# SHIELD_W5500.net
KiCad netlist of a schematic drawn in Altium Designer
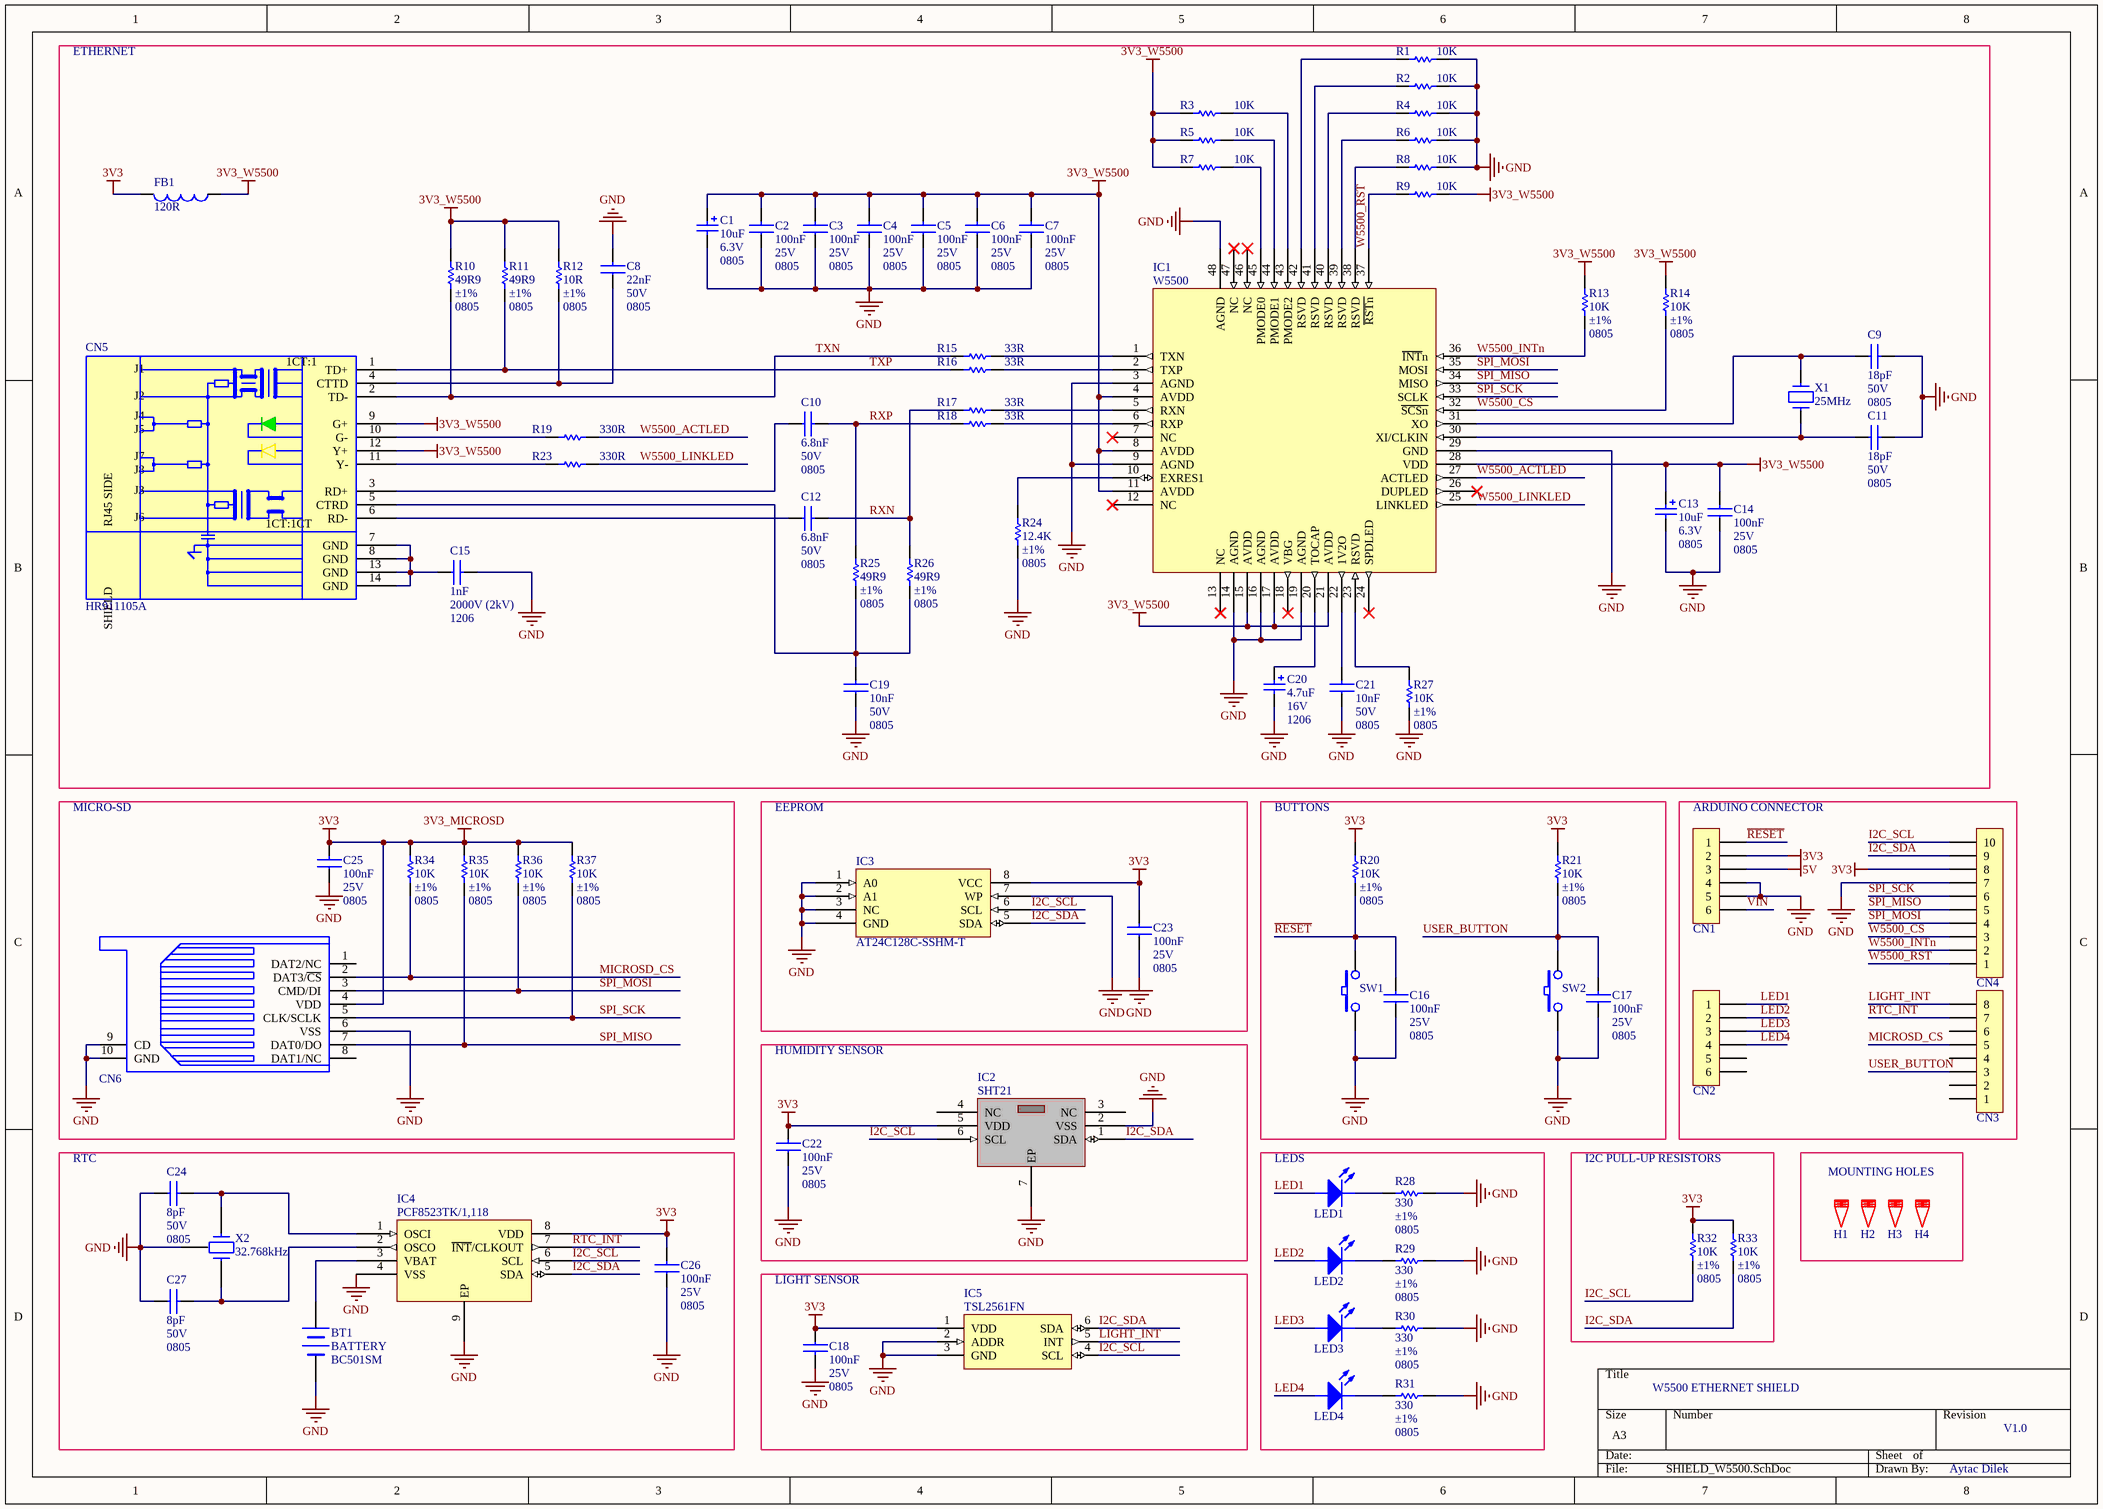
[diagram p0: SHIELD_W5500.SchDoc]

(export (version "E")
  (design (tool "Eeschema 10.0.6"))
  (components
    (comp (ref "BT1")
      (value "BATTERY")
      (footprint "MPD_BC501SM")
      (description "HOLDER COIN CELL FOR CR1220 SMD")
      (fields
        (field (name "PART NUMBER") "SBAT00011")
        (field (name "MANUFACTURER PART NUMBER") "BC501SM")
        (field (name "VOLTAGE") "3V")
      )
      (libsource (lib "ComponentDatabase") (part "BATTERY"))
    )
    (comp (ref "C1")
      (value "10uF")
      (footprint "CAPMP2013X12N_EIA-0805_CASE-R")
      (description "CAP TANT 10UF 6.3V 10% 0805")
      (fields
        (field (name "PART NUMBER") "SCAP01400004")
        (field (name "TOLERANCE") "±10%")
        (field (name "VOLTAGE - RATED") "6.3V")
        (field (name "PACKAGE / CASE") "0805")
      )
      (libsource (lib "ComponentDatabase") (part "CAP_P"))
    )
    (comp (ref "C2")
      (value "CAP_NP")
      (footprint "CAPC2012X100N_EIA0805")
      (description "CAP CER 0.1UF 25V X7R 0805")
      (fields
        (field (name "PART NUMBER") "SCAP00300093")
        (field (name "CAPACITANCE") "100nF")
        (field (name "TOLERANCE") "±10%")
        (field (name "VOLTAGE - RATED") "25V")
        (field (name "PACKAGE / CASE") "0805")
      )
      (libsource (lib "ComponentDatabase") (part "CAP_NP"))
    )
    (comp (ref "C3")
      (value "CAP_NP")
      (footprint "CAPC2012X100N_EIA0805")
      (description "CAP CER 0.1UF 25V X7R 0805")
      (fields
        (field (name "PART NUMBER") "SCAP00300093")
        (field (name "CAPACITANCE") "100nF")
        (field (name "TOLERANCE") "±10%")
        (field (name "VOLTAGE - RATED") "25V")
        (field (name "PACKAGE / CASE") "0805")
      )
      (libsource (lib "ComponentDatabase") (part "CAP_NP"))
    )
    (comp (ref "C4")
      (value "CAP_NP")
      (footprint "CAPC2012X100N_EIA0805")
      (description "CAP CER 0.1UF 25V X7R 0805")
      (fields
        (field (name "PART NUMBER") "SCAP00300093")
        (field (name "CAPACITANCE") "100nF")
        (field (name "TOLERANCE") "±10%")
        (field (name "VOLTAGE - RATED") "25V")
        (field (name "PACKAGE / CASE") "0805")
      )
      (libsource (lib "ComponentDatabase") (part "CAP_NP"))
    )
    (comp (ref "C5")
      (value "CAP_NP")
      (footprint "CAPC2012X100N_EIA0805")
      (description "CAP CER 0.1UF 25V X7R 0805")
      (fields
        (field (name "PART NUMBER") "SCAP00300093")
        (field (name "CAPACITANCE") "100nF")
        (field (name "TOLERANCE") "±10%")
        (field (name "VOLTAGE - RATED") "25V")
        (field (name "PACKAGE / CASE") "0805")
      )
      (libsource (lib "ComponentDatabase") (part "CAP_NP"))
    )
    (comp (ref "C6")
      (value "CAP_NP")
      (footprint "CAPC2012X100N_EIA0805")
      (description "CAP CER 0.1UF 25V X7R 0805")
      (fields
        (field (name "PART NUMBER") "SCAP00300093")
        (field (name "CAPACITANCE") "100nF")
        (field (name "TOLERANCE") "±10%")
        (field (name "VOLTAGE - RATED") "25V")
        (field (name "PACKAGE / CASE") "0805")
      )
      (libsource (lib "ComponentDatabase") (part "CAP_NP"))
    )
    (comp (ref "C7")
      (value "CAP_NP")
      (footprint "CAPC2012X100N_EIA0805")
      (description "CAP CER 0.1UF 25V X7R 0805")
      (fields
        (field (name "PART NUMBER") "SCAP00300093")
        (field (name "CAPACITANCE") "100nF")
        (field (name "TOLERANCE") "±10%")
        (field (name "VOLTAGE - RATED") "25V")
        (field (name "PACKAGE / CASE") "0805")
      )
      (libsource (lib "ComponentDatabase") (part "CAP_NP"))
    )
    (comp (ref "C8")
      (value "CAP_NP")
      (footprint "CAPC2012X100N_EIA0805")
      (description "CAP CER 0.022UF 50V X7R 0805")
      (fields
        (field (name "PART NUMBER") "SCAP00300087")
        (field (name "CAPACITANCE") "22nF")
        (field (name "TOLERANCE") "±10%")
        (field (name "VOLTAGE - RATED") "50V")
        (field (name "PACKAGE / CASE") "0805")
      )
      (libsource (lib "ComponentDatabase") (part "CAP_NP"))
    )
    (comp (ref "C9")
      (value "CAP_NP")
      (footprint "CAPC2012X100N_EIA0805")
      (description "CAP CER 18PF 50V NP0 0805")
      (fields
        (field (name "PART NUMBER") "SCAP00300040")
        (field (name "CAPACITANCE") "18pF")
        (field (name "TOLERANCE") "±5%")
        (field (name "VOLTAGE - RATED") "50V")
        (field (name "PACKAGE / CASE") "0805")
      )
      (libsource (lib "ComponentDatabase") (part "CAP_NP"))
    )
    (comp (ref "C10")
      (value "CAP_NP")
      (footprint "CAPC2012X100N_EIA0805")
      (description "CAP CER 6800PF 50V X7R 0805")
      (fields
        (field (name "PART NUMBER") "SCAP00300083")
        (field (name "CAPACITANCE") "6.8nF")
        (field (name "TOLERANCE") "±10%")
        (field (name "VOLTAGE - RATED") "50V")
        (field (name "PACKAGE / CASE") "0805")
      )
      (libsource (lib "ComponentDatabase") (part "CAP_NP"))
    )
    (comp (ref "C11")
      (value "CAP_NP")
      (footprint "CAPC2012X100N_EIA0805")
      (description "CAP CER 18PF 50V NP0 0805")
      (fields
        (field (name "PART NUMBER") "SCAP00300040")
        (field (name "CAPACITANCE") "18pF")
        (field (name "TOLERANCE") "±5%")
        (field (name "VOLTAGE - RATED") "50V")
        (field (name "PACKAGE / CASE") "0805")
      )
      (libsource (lib "ComponentDatabase") (part "CAP_NP"))
    )
    (comp (ref "C12")
      (value "CAP_NP")
      (footprint "CAPC2012X100N_EIA0805")
      (description "CAP CER 6800PF 50V X7R 0805")
      (fields
        (field (name "PART NUMBER") "SCAP00300083")
        (field (name "CAPACITANCE") "6.8nF")
        (field (name "TOLERANCE") "±10%")
        (field (name "VOLTAGE - RATED") "50V")
        (field (name "PACKAGE / CASE") "0805")
      )
      (libsource (lib "ComponentDatabase") (part "CAP_NP"))
    )
    (comp (ref "C13")
      (value "10uF")
      (footprint "CAPMP2013X12N_EIA-0805_CASE-R")
      (description "CAP TANT 10UF 6.3V 10% 0805")
      (fields
        (field (name "PART NUMBER") "SCAP01400004")
        (field (name "TOLERANCE") "±10%")
        (field (name "VOLTAGE - RATED") "6.3V")
        (field (name "PACKAGE / CASE") "0805")
      )
      (libsource (lib "ComponentDatabase") (part "CAP_P"))
    )
    (comp (ref "C14")
      (value "CAP_NP")
      (footprint "CAPC2012X100N_EIA0805")
      (description "CAP CER 0.1UF 25V X7R 0805")
      (fields
        (field (name "PART NUMBER") "SCAP00300093")
        (field (name "CAPACITANCE") "100nF")
        (field (name "TOLERANCE") "±10%")
        (field (name "VOLTAGE - RATED") "25V")
        (field (name "PACKAGE / CASE") "0805")
      )
      (libsource (lib "ComponentDatabase") (part "CAP_NP"))
    )
    (comp (ref "C15")
      (value "1nF")
      (footprint "CAPC3216X125N_EIA1206")
      (description "CAP CER 1000PF 2KV X7R 1206")
      (fields
        (field (name "PART NUMBER") "SCAP00410036")
        (field (name "TOLERANCE") "±10%")
        (field (name "VOLTAGE - RATED") "2000V (2kV)")
        (field (name "PACKAGE / CASE") "1206")
      )
      (libsource (lib "ComponentDatabase") (part "CAP_NP"))
    )
    (comp (ref "C16")
      (value "CAP_NP")
      (footprint "CAPC2012X100N_EIA0805")
      (description "CAP CER 0.1UF 25V X7R 0805")
      (fields
        (field (name "PART NUMBER") "SCAP00300093")
        (field (name "CAPACITANCE") "100nF")
        (field (name "VOLTAGE - RATED") "25V")
        (field (name "PACKAGE / CASE") "0805")
        (field (name "TOLERANCE") "±10%")
      )
      (libsource (lib "ComponentDatabase") (part "CAP_NP"))
    )
    (comp (ref "C17")
      (value "CAP_NP")
      (footprint "CAPC2012X100N_EIA0805")
      (description "CAP CER 0.1UF 25V X7R 0805")
      (fields
        (field (name "PART NUMBER") "SCAP00300093")
        (field (name "CAPACITANCE") "100nF")
        (field (name "VOLTAGE - RATED") "25V")
        (field (name "PACKAGE / CASE") "0805")
        (field (name "TOLERANCE") "±10%")
      )
      (libsource (lib "ComponentDatabase") (part "CAP_NP"))
    )
    (comp (ref "C18")
      (value "CAP_NP")
      (footprint "CAPC2012X100N_EIA0805")
      (description "CAP CER 0.1UF 25V X7R 0805")
      (fields
        (field (name "PART NUMBER") "SCAP00300093")
        (field (name "CAPACITANCE") "100nF")
        (field (name "TOLERANCE") "±10%")
        (field (name "VOLTAGE - RATED") "25V")
        (field (name "PACKAGE / CASE") "0805")
      )
      (libsource (lib "ComponentDatabase") (part "CAP_NP"))
    )
    (comp (ref "C19")
      (value "CAP_NP")
      (footprint "CAPC2012X100N_EIA0805")
      (description "CAP CER 10000PF 50V X7R 0805")
      (fields
        (field (name "PART NUMBER") "SCAP00300085")
        (field (name "CAPACITANCE") "10nF")
        (field (name "TOLERANCE") "±10%")
        (field (name "VOLTAGE - RATED") "50V")
        (field (name "PACKAGE / CASE") "0805")
      )
      (libsource (lib "ComponentDatabase") (part "CAP_NP"))
    )
    (comp (ref "C20")
      (value "4.7uF")
      (footprint "CAPMP3216X16N_EIA-1206_CASE-A")
      (description "CAP TANT 4.7UF 16V 10% 1206")
      (fields
        (field (name "PART NUMBER") "SCAP01400003")
        (field (name "TOLERANCE") "±10%")
        (field (name "VOLTAGE - RATED") "16V")
        (field (name "PACKAGE / CASE") "1206")
      )
      (libsource (lib "ComponentDatabase") (part "CAP_P"))
    )
    (comp (ref "C21")
      (value "CAP_NP")
      (footprint "CAPC2012X100N_EIA0805")
      (description "CAP CER 10000PF 50V X7R 0805")
      (fields
        (field (name "PART NUMBER") "SCAP00300085")
        (field (name "CAPACITANCE") "10nF")
        (field (name "TOLERANCE") "±10%")
        (field (name "VOLTAGE - RATED") "50V")
        (field (name "PACKAGE / CASE") "0805")
      )
      (libsource (lib "ComponentDatabase") (part "CAP_NP"))
    )
    (comp (ref "C22")
      (value "CAP_NP")
      (footprint "CAPC2012X100N_EIA0805")
      (description "CAP CER 0.1UF 25V X7R 0805")
      (fields
        (field (name "PART NUMBER") "SCAP00300093")
        (field (name "CAPACITANCE") "100nF")
        (field (name "TOLERANCE") "±10%")
        (field (name "VOLTAGE - RATED") "25V")
        (field (name "PACKAGE / CASE") "0805")
      )
      (libsource (lib "ComponentDatabase") (part "CAP_NP"))
    )
    (comp (ref "C23")
      (value "CAP_NP")
      (footprint "CAPC2012X100N_EIA0805")
      (description "CAP CER 0.1UF 25V X7R 0805")
      (fields
        (field (name "PART NUMBER") "SCAP00300093")
        (field (name "CAPACITANCE") "100nF")
        (field (name "VOLTAGE - RATED") "25V")
        (field (name "PACKAGE / CASE") "0805")
        (field (name "TOLERANCE") "±10%")
      )
      (libsource (lib "ComponentDatabase") (part "CAP_NP"))
    )
    (comp (ref "C24")
      (value "CAP_NP")
      (footprint "CAPC2012X100N_EIA0805")
      (description "CAP CER 8PF 50V NP0 0805")
      (fields
        (field (name "PART NUMBER") "SCAP00300030")
        (field (name "CAPACITANCE") "8pF")
        (field (name "VOLTAGE - RATED") "50V")
        (field (name "PACKAGE / CASE") "0805")
        (field (name "TOLERANCE") "±0.25pF")
      )
      (libsource (lib "ComponentDatabase") (part "CAP_NP"))
    )
    (comp (ref "C25")
      (value "CAP_NP")
      (footprint "CAPC2012X100N_EIA0805")
      (description "CAP CER 0.1UF 25V X7R 0805")
      (fields
        (field (name "PART NUMBER") "SCAP00300093")
        (field (name "CAPACITANCE") "100nF")
        (field (name "VOLTAGE - RATED") "25V")
        (field (name "PACKAGE / CASE") "0805")
        (field (name "TOLERANCE") "±10%")
      )
      (libsource (lib "ComponentDatabase") (part "CAP_NP"))
    )
    (comp (ref "C26")
      (value "CAP_NP")
      (footprint "CAPC2012X100N_EIA0805")
      (description "CAP CER 0.1UF 25V X7R 0805")
      (fields
        (field (name "PART NUMBER") "SCAP00300093")
        (field (name "CAPACITANCE") "100nF")
        (field (name "VOLTAGE - RATED") "25V")
        (field (name "PACKAGE / CASE") "0805")
        (field (name "TOLERANCE") "±10%")
      )
      (libsource (lib "ComponentDatabase") (part "CAP_NP"))
    )
    (comp (ref "C27")
      (value "CAP_NP")
      (footprint "CAPC2012X100N_EIA0805")
      (description "CAP CER 8PF 50V NP0 0805")
      (fields
        (field (name "PART NUMBER") "SCAP00300030")
        (field (name "CAPACITANCE") "8pF")
        (field (name "VOLTAGE - RATED") "50V")
        (field (name "PACKAGE / CASE") "0805")
        (field (name "TOLERANCE") "±0.25pF")
      )
      (libsource (lib "ComponentDatabase") (part "CAP_NP"))
    )
    (comp (ref "CN1")
      (value "HDR_1X6")
      (footprint "HDRFV6W70P254_1X6_1524X254X1118P")
      (description "CONN ARDUINO HEADER .0100\" 6POS")
      (fields (field (name "PART NUMBER") "SCON00124"))
      (libsource (lib "ComponentDatabase") (part "HDR_1X6"))
    )
    (comp (ref "CN2")
      (value "HDR_1X6")
      (footprint "HDRFV6W70P254_1X6_1524X254X1118P")
      (description "CONN ARDUINO HEADER .0100\" 6POS")
      (fields (field (name "PART NUMBER") "SCON00124"))
      (libsource (lib "ComponentDatabase") (part "HDR_1X6"))
    )
    (comp (ref "CN3")
      (value "HDR_1X8")
      (footprint "HDRFV8W70P254_1X8_2032X254X1118P")
      (description "CONN ARDUINO HEADER .0100\" 8POS")
      (fields (field (name "PART NUMBER") "SCON00125"))
      (libsource (lib "ComponentDatabase") (part "HDR_1X8"))
    )
    (comp (ref "CN4")
      (value "HDR_1X10")
      (footprint "HDRFV10W70P254_1X10_2540X254X1118P")
      (description "CONN ARDUINO HEADER .0100\" 10POS")
      (fields (field (name "PART NUMBER") "SCON00126"))
      (libsource (lib "ComponentDatabase") (part "HDR_1X10"))
    )
    (comp (ref "CN5")
      (value "HR911105A")
      (footprint "HANRUN_HR911105A")
      (description "CONN MAGJACK 1PORT 100 BASE-T")
      (fields (field (name "PART NUMBER") "SCON00127"))
      (libsource (lib "ComponentDatabase") (part "HR911105A"))
    )
    (comp (ref "CN6")
      (value "MICRO-SD")
      (footprint "MICRO-SD-SELF-EJECT")
      (description "CONN MICRO SD CARD PUSH-PUSH R/A")
      (fields (field (name "PART NUMBER") "SCON00094") (field (name "MANUFACTURER") "TransFlash"))
      (libsource (lib "ComponentDatabase") (part "MICRO-SD"))
    )
    (comp (ref "FB1")
      (value "BEAD")
      (footprint "FILC2012X100N_EIA0805")
      (description "FERRITE CHIP POWER 120 OHM SMD")
      (fields
        (field (name "PART NUMBER") "SFIL00005")
        (field (name "IMPEDANCE") "120R")
        (field (name "MANUFACTURER") "Laird-Signal Integrity Products")
      )
      (libsource (lib "ComponentDatabase") (part "BEAD"))
    )
    (comp (ref "H1")
      (value "HOLES")
      (footprint "HOLE_125MIL")
      (description "Holes")
      (fields (field (name "PART NUMBER") "SMSC00005"))
      (libsource (lib "ComponentDatabase") (part "HOLES"))
    )
    (comp (ref "H2")
      (value "HOLES")
      (footprint "HOLE_125MIL")
      (description "Holes")
      (fields (field (name "PART NUMBER") "SMSC00005"))
      (libsource (lib "ComponentDatabase") (part "HOLES"))
    )
    (comp (ref "H3")
      (value "HOLES")
      (footprint "HOLE_125MIL")
      (description "Holes")
      (fields (field (name "PART NUMBER") "SMSC00005"))
      (libsource (lib "ComponentDatabase") (part "HOLES"))
    )
    (comp (ref "H4")
      (value "HOLES")
      (footprint "HOLE_125MIL")
      (description "Holes")
      (fields (field (name "PART NUMBER") "SMSC00005"))
      (libsource (lib "ComponentDatabase") (part "HOLES"))
    )
    (comp (ref "IC1")
      (value "W5500")
      (footprint "QFP50P900X900X160-48N")
      (description "IC CTLR 3-1 ETH TCP/IP 48LQFP")
      (fields
        (field (name "PART NUMBER") "SIC00138")
        (field (name "MANUFACTURER PART NUMBER") "W5500")
        (field (name "MANUFACTURER") "WIZnet")
      )
      (libsource (lib "ComponentDatabase") (part "W5500"))
    )
    (comp (ref "IC2")
      (value "SHT21")
      (footprint "SHT21")
      (description "HUMIDITY AND TEMPERATURE SENSOR")
      (fields
        (field (name "PART NUMBER") "SSEN00014")
        (field (name "VOLTAGE") "2.1 V ~ 3.6 V")
        (field (name "MANUFACTURER PART NUMBER") "SHT21")
      )
      (libsource (lib "ComponentDatabase") (part "SHT21"))
    )
    (comp (ref "IC3")
      (value "AT24C128")
      (footprint "SOIC127P600X175-8N")
      (description "IC EEPROM 128KBIT 1MHZ 8SOIC")
      (fields
        (field (name "PART NUMBER") "SMEM00014")
        (field (name "VOLTAGE") "1.7 V ~ 5.5 V")
        (field (name "MANUFACTURER PART NUMBER") "AT24C128C-SSHM-T")
      )
      (libsource (lib "ComponentDatabase") (part "AT24C128"))
    )
    (comp (ref "IC4")
      (value "PCF8523TK/1,118")
      (footprint "SON80P400X100_HS-9N_[NXP]SOT909-1")
      (description "IC RTC CLK/CALENDAR I2C 8-HVSON")
      (fields
        (field (name "PART NUMBER") "SIC00133")
        (field (name "MANUFACTURER PART NUMBER") "PCF8523TK/1,118")
        (field (name "MANUFACTURER") "NXP Semiconductors")
      )
      (libsource (lib "ComponentDatabase") (part "PCF8523TK/1,118"))
    )
    (comp (ref "IC5")
      (value "TSL256x")
      (footprint "DFN-6")
      (description "IC LIGHT TO DGTL CONV 6-DFN")
      (fields
        (field (name "PART NUMBER") "SSEN00013")
        (field (name "VOLTAGE") "2.7 V ~ 3.6 V")
        (field (name "MANUFACTURER PART NUMBER") "TSL2561FN")
      )
      (libsource (lib "ComponentDatabase") (part "TSL256x"))
    )
    (comp (ref "LED1")
      (value "LED")
      (footprint "LEDC2012X70N_EIA0805_RED")
      (description "LED SUPER RED CLR THIN 0805 SMD")
      (fields (field (name "PART NUMBER") "SOPT00004") (field (name "MANUFACTURER") "Lite-On Inc"))
      (libsource (lib "ComponentDatabase") (part "LED"))
    )
    (comp (ref "LED2")
      (value "LED")
      (footprint "LEDC2012X70N_EIA0805_RED")
      (description "LED SUPER RED CLR THIN 0805 SMD")
      (fields (field (name "PART NUMBER") "SOPT00004") (field (name "MANUFACTURER") "Lite-On Inc"))
      (libsource (lib "ComponentDatabase") (part "LED"))
    )
    (comp (ref "LED3")
      (value "LED")
      (footprint "LEDC2012X70N_EIA0805_RED")
      (description "LED SUPER RED CLR THIN 0805 SMD")
      (fields (field (name "PART NUMBER") "SOPT00004") (field (name "MANUFACTURER") "Lite-On Inc"))
      (libsource (lib "ComponentDatabase") (part "LED"))
    )
    (comp (ref "LED4")
      (value "LED")
      (footprint "LEDC2012X70N_EIA0805_RED")
      (description "LED SUPER RED CLR THIN 0805 SMD")
      (fields (field (name "PART NUMBER") "SOPT00004") (field (name "MANUFACTURER") "Lite-On Inc"))
      (libsource (lib "ComponentDatabase") (part "LED"))
    )
    (comp (ref "R1")
      (value "10K")
      (footprint "RESC2013X65N_EIA0805")
      (description "RES SMD 10K OHM 1% 1/8W 0805")
      (fields (field (name "PART NUMBER") "SRES03010098") (field (name "TOLERANCE") "±1%"))
      (libsource (lib "ComponentDatabase") (part "RES"))
    )
    (comp (ref "R2")
      (value "10K")
      (footprint "RESC2013X65N_EIA0805")
      (description "RES SMD 10K OHM 1% 1/8W 0805")
      (fields (field (name "PART NUMBER") "SRES03010098") (field (name "TOLERANCE") "±1%"))
      (libsource (lib "ComponentDatabase") (part "RES"))
    )
    (comp (ref "R3")
      (value "10K")
      (footprint "RESC2013X65N_EIA0805")
      (description "RES SMD 10K OHM 1% 1/8W 0805")
      (fields (field (name "PART NUMBER") "SRES03010098") (field (name "TOLERANCE") "±1%"))
      (libsource (lib "ComponentDatabase") (part "RES"))
    )
    (comp (ref "R4")
      (value "10K")
      (footprint "RESC2013X65N_EIA0805")
      (description "RES SMD 10K OHM 1% 1/8W 0805")
      (fields (field (name "PART NUMBER") "SRES03010098") (field (name "TOLERANCE") "±1%"))
      (libsource (lib "ComponentDatabase") (part "RES"))
    )
    (comp (ref "R5")
      (value "10K")
      (footprint "RESC2013X65N_EIA0805")
      (description "RES SMD 10K OHM 1% 1/8W 0805")
      (fields (field (name "PART NUMBER") "SRES03010098") (field (name "TOLERANCE") "±1%"))
      (libsource (lib "ComponentDatabase") (part "RES"))
    )
    (comp (ref "R6")
      (value "10K")
      (footprint "RESC2013X65N_EIA0805")
      (description "RES SMD 10K OHM 1% 1/8W 0805")
      (fields (field (name "PART NUMBER") "SRES03010098") (field (name "TOLERANCE") "±1%"))
      (libsource (lib "ComponentDatabase") (part "RES"))
    )
    (comp (ref "R7")
      (value "10K")
      (footprint "RESC2013X65N_EIA0805")
      (description "RES SMD 10K OHM 1% 1/8W 0805")
      (fields (field (name "PART NUMBER") "SRES03010098") (field (name "TOLERANCE") "±1%"))
      (libsource (lib "ComponentDatabase") (part "RES"))
    )
    (comp (ref "R8")
      (value "10K")
      (footprint "RESC2013X65N_EIA0805")
      (description "RES SMD 10K OHM 1% 1/8W 0805")
      (fields (field (name "PART NUMBER") "SRES03010098") (field (name "TOLERANCE") "±1%"))
      (libsource (lib "ComponentDatabase") (part "RES"))
    )
    (comp (ref "R9")
      (value "10K")
      (footprint "RESC2013X65N_EIA0805")
      (description "RES SMD 10K OHM 1% 1/8W 0805")
      (fields (field (name "PART NUMBER") "SRES03010098") (field (name "TOLERANCE") "±1%"))
      (libsource (lib "ComponentDatabase") (part "RES"))
    )
    (comp (ref "R10")
      (value "49R9")
      (footprint "RESC2013X65N_EIA0805")
      (description "RES SMD 49.9 OHM 1% 1/8W 0805")
      (fields
        (field (name "PART NUMBER") "SRES03030081")
        (field (name "TOLERANCE") "±1%")
        (field (name "PACKAGE / CASE") "0805")
        (field (name "MANUFACTURER") "Samsung Electro-Mechanics America, Inc.")
      )
      (libsource (lib "ComponentDatabase") (part "RES"))
    )
    (comp (ref "R11")
      (value "49R9")
      (footprint "RESC2013X65N_EIA0805")
      (description "RES SMD 49.9 OHM 1% 1/8W 0805")
      (fields
        (field (name "PART NUMBER") "SRES03030081")
        (field (name "TOLERANCE") "±1%")
        (field (name "PACKAGE / CASE") "0805")
        (field (name "MANUFACTURER") "Samsung Electro-Mechanics America, Inc.")
      )
      (libsource (lib "ComponentDatabase") (part "RES"))
    )
    (comp (ref "R12")
      (value "10R")
      (footprint "RESC2013X65N_EIA0805")
      (description "RES SMD 10 OHM 1% 1/8W 0805")
      (fields
        (field (name "PART NUMBER") "SRES03010026")
        (field (name "TOLERANCE") "±1%")
        (field (name "PACKAGE / CASE") "0805")
        (field (name "MANUFACTURER") "Yageo")
      )
      (libsource (lib "ComponentDatabase") (part "RES"))
    )
    (comp (ref "R13")
      (value "10K")
      (footprint "RESC2013X65N_EIA0805")
      (description "RES SMD 10K OHM 1% 1/8W 0805")
      (fields
        (field (name "PART NUMBER") "SRES03010098")
        (field (name "TOLERANCE") "±1%")
        (field (name "PACKAGE / CASE") "0805")
        (field (name "MANUFACTURER") "Yageo")
      )
      (libsource (lib "ComponentDatabase") (part "RES"))
    )
    (comp (ref "R14")
      (value "10K")
      (footprint "RESC2013X65N_EIA0805")
      (description "RES SMD 10K OHM 1% 1/8W 0805")
      (fields
        (field (name "PART NUMBER") "SRES03010098")
        (field (name "TOLERANCE") "±1%")
        (field (name "PACKAGE / CASE") "0805")
        (field (name "MANUFACTURER") "Yageo")
      )
      (libsource (lib "ComponentDatabase") (part "RES"))
    )
    (comp (ref "R15")
      (value "33R")
      (footprint "RESC2013X65N_EIA0805")
      (description "RES SMD 33 OHM 1% 1/8W 0805")
      (fields (field (name "PART NUMBER") "SRES03010038") (field (name "TOLERANCE") "±1%"))
      (libsource (lib "ComponentDatabase") (part "RES"))
    )
    (comp (ref "R16")
      (value "33R")
      (footprint "RESC2013X65N_EIA0805")
      (description "RES SMD 33 OHM 1% 1/8W 0805")
      (fields (field (name "PART NUMBER") "SRES03010038") (field (name "TOLERANCE") "±1%"))
      (libsource (lib "ComponentDatabase") (part "RES"))
    )
    (comp (ref "R17")
      (value "33R")
      (footprint "RESC2013X65N_EIA0805")
      (description "RES SMD 33 OHM 1% 1/8W 0805")
      (fields (field (name "PART NUMBER") "SRES03010038") (field (name "TOLERANCE") "±1%"))
      (libsource (lib "ComponentDatabase") (part "RES"))
    )
    (comp (ref "R18")
      (value "33R")
      (footprint "RESC2013X65N_EIA0805")
      (description "RES SMD 33 OHM 1% 1/8W 0805")
      (fields (field (name "PART NUMBER") "SRES03010038") (field (name "TOLERANCE") "±1%"))
      (libsource (lib "ComponentDatabase") (part "RES"))
    )
    (comp (ref "R19")
      (value "330R")
      (footprint "RESC2013X65N_EIA0805")
      (description "RES SMD 330 OHM 1% 1/8W 0805")
      (fields (field (name "PART NUMBER") "SRES03010062") (field (name "TOLERANCE") "±1%"))
      (libsource (lib "ComponentDatabase") (part "RES"))
    )
    (comp (ref "R20")
      (value "RES")
      (footprint "RESC2013X65N_EIA0805")
      (description "RES SMD 10K OHM 1% 1/8W 0805")
      (fields
        (field (name "PART NUMBER") "SRES03010098")
        (field (name "RESISTANCE (OHM)") "10K")
        (field (name "TOLERANCE") "±1%")
        (field (name "PACKAGE / CASE") "0805")
        (field (name "MANUFACTURER") "Yageo")
      )
      (libsource (lib "ComponentDatabase") (part "RES"))
    )
    (comp (ref "R21")
      (value "RES")
      (footprint "RESC2013X65N_EIA0805")
      (description "RES SMD 10K OHM 1% 1/8W 0805")
      (fields
        (field (name "PART NUMBER") "SRES03010098")
        (field (name "RESISTANCE (OHM)") "10K")
        (field (name "TOLERANCE") "±1%")
        (field (name "PACKAGE / CASE") "0805")
        (field (name "MANUFACTURER") "Yageo")
      )
      (libsource (lib "ComponentDatabase") (part "RES"))
    )
    (comp (ref "R23")
      (value "330R")
      (footprint "RESC2013X65N_EIA0805")
      (description "RES SMD 330 OHM 1% 1/8W 0805")
      (fields (field (name "PART NUMBER") "SRES03010062") (field (name "TOLERANCE") "±1%"))
      (libsource (lib "ComponentDatabase") (part "RES"))
    )
    (comp (ref "R24")
      (value "12.4K")
      (footprint "RESC2013X65N_EIA0805")
      (description "RES SMD 12.4K OHM 1% 1/8W 0805")
      (fields
        (field (name "PART NUMBER") "SRES03010171")
        (field (name "TOLERANCE") "±1%")
        (field (name "PACKAGE / CASE") "0805")
        (field (name "MANUFACTURER") "Yageo")
      )
      (libsource (lib "ComponentDatabase") (part "RES"))
    )
    (comp (ref "R25")
      (value "49R9")
      (footprint "RESC2013X65N_EIA0805")
      (description "RES SMD 49.9 OHM 1% 1/8W 0805")
      (fields
        (field (name "PART NUMBER") "SRES03030081")
        (field (name "TOLERANCE") "±1%")
        (field (name "PACKAGE / CASE") "0805")
        (field (name "MANUFACTURER") "Samsung Electro-Mechanics America, Inc.")
      )
      (libsource (lib "ComponentDatabase") (part "RES"))
    )
    (comp (ref "R26")
      (value "49R9")
      (footprint "RESC2013X65N_EIA0805")
      (description "RES SMD 49.9 OHM 1% 1/8W 0805")
      (fields
        (field (name "PART NUMBER") "SRES03030081")
        (field (name "TOLERANCE") "±1%")
        (field (name "PACKAGE / CASE") "0805")
        (field (name "MANUFACTURER") "Samsung Electro-Mechanics America, Inc.")
      )
      (libsource (lib "ComponentDatabase") (part "RES"))
    )
    (comp (ref "R27")
      (value "10K")
      (footprint "RESC2013X65N_EIA0805")
      (description "RES SMD 10K OHM 1% 1/8W 0805")
      (fields
        (field (name "PART NUMBER") "SRES03010098")
        (field (name "TOLERANCE") "±1%")
        (field (name "PACKAGE / CASE") "0805")
        (field (name "MANUFACTURER") "Yageo")
      )
      (libsource (lib "ComponentDatabase") (part "RES"))
    )
    (comp (ref "R28")
      (value "RES")
      (footprint "RESC2013X65N_EIA0805")
      (description "RES SMD 330 OHM 1% 1/8W 0805")
      (fields
        (field (name "PART NUMBER") "SRES03010062")
        (field (name "RESISTANCE (OHM)") "330")
        (field (name "TOLERANCE") "±1%")
        (field (name "PACKAGE / CASE") "0805")
        (field (name "MANUFACTURER") "Yageo")
      )
      (libsource (lib "ComponentDatabase") (part "RES"))
    )
    (comp (ref "R29")
      (value "RES")
      (footprint "RESC2013X65N_EIA0805")
      (description "RES SMD 330 OHM 1% 1/8W 0805")
      (fields
        (field (name "PART NUMBER") "SRES03010062")
        (field (name "RESISTANCE (OHM)") "330")
        (field (name "TOLERANCE") "±1%")
        (field (name "PACKAGE / CASE") "0805")
        (field (name "MANUFACTURER") "Yageo")
      )
      (libsource (lib "ComponentDatabase") (part "RES"))
    )
    (comp (ref "R30")
      (value "RES")
      (footprint "RESC2013X65N_EIA0805")
      (description "RES SMD 330 OHM 1% 1/8W 0805")
      (fields
        (field (name "PART NUMBER") "SRES03010062")
        (field (name "RESISTANCE (OHM)") "330")
        (field (name "TOLERANCE") "±1%")
        (field (name "PACKAGE / CASE") "0805")
        (field (name "MANUFACTURER") "Yageo")
      )
      (libsource (lib "ComponentDatabase") (part "RES"))
    )
    (comp (ref "R31")
      (value "RES")
      (footprint "RESC2013X65N_EIA0805")
      (description "RES SMD 330 OHM 1% 1/8W 0805")
      (fields
        (field (name "PART NUMBER") "SRES03010062")
        (field (name "RESISTANCE (OHM)") "330")
        (field (name "TOLERANCE") "±1%")
        (field (name "PACKAGE / CASE") "0805")
        (field (name "MANUFACTURER") "Yageo")
      )
      (libsource (lib "ComponentDatabase") (part "RES"))
    )
    (comp (ref "R32")
      (value "RES")
      (footprint "RESC2013X65N_EIA0805")
      (description "RES SMD 10K OHM 1% 1/8W 0805")
      (fields
        (field (name "PART NUMBER") "SRES03010098")
        (field (name "RESISTANCE (OHM)") "10K")
        (field (name "TOLERANCE") "±1%")
        (field (name "PACKAGE / CASE") "0805")
        (field (name "MANUFACTURER") "Yageo")
      )
      (libsource (lib "ComponentDatabase") (part "RES"))
    )
    (comp (ref "R33")
      (value "RES")
      (footprint "RESC2013X65N_EIA0805")
      (description "RES SMD 10K OHM 1% 1/8W 0805")
      (fields
        (field (name "PART NUMBER") "SRES03010098")
        (field (name "RESISTANCE (OHM)") "10K")
        (field (name "TOLERANCE") "±1%")
        (field (name "PACKAGE / CASE") "0805")
        (field (name "MANUFACTURER") "Yageo")
      )
      (libsource (lib "ComponentDatabase") (part "RES"))
    )
    (comp (ref "R34")
      (value "RES")
      (footprint "RESC2013X65N_EIA0805")
      (description "RES SMD 10K OHM 1% 1/8W 0805")
      (fields
        (field (name "PART NUMBER") "SRES03010098")
        (field (name "RESISTANCE (OHM)") "10K")
        (field (name "TOLERANCE") "±1%")
        (field (name "PACKAGE / CASE") "0805")
        (field (name "MANUFACTURER") "Yageo")
      )
      (libsource (lib "ComponentDatabase") (part "RES"))
    )
    (comp (ref "R35")
      (value "RES")
      (footprint "RESC2013X65N_EIA0805")
      (description "RES SMD 10K OHM 1% 1/8W 0805")
      (fields
        (field (name "PART NUMBER") "SRES03010098")
        (field (name "RESISTANCE (OHM)") "10K")
        (field (name "TOLERANCE") "±1%")
        (field (name "PACKAGE / CASE") "0805")
        (field (name "MANUFACTURER") "Yageo")
      )
      (libsource (lib "ComponentDatabase") (part "RES"))
    )
    (comp (ref "R36")
      (value "RES")
      (footprint "RESC2013X65N_EIA0805")
      (description "RES SMD 10K OHM 1% 1/8W 0805")
      (fields
        (field (name "PART NUMBER") "SRES03010098")
        (field (name "RESISTANCE (OHM)") "10K")
        (field (name "TOLERANCE") "±1%")
        (field (name "PACKAGE / CASE") "0805")
        (field (name "MANUFACTURER") "Yageo")
      )
      (libsource (lib "ComponentDatabase") (part "RES"))
    )
    (comp (ref "R37")
      (value "RES")
      (footprint "RESC2013X65N_EIA0805")
      (description "RES SMD 10K OHM 1% 1/8W 0805")
      (fields
        (field (name "PART NUMBER") "SRES03010098")
        (field (name "RESISTANCE (OHM)") "10K")
        (field (name "TOLERANCE") "±1%")
        (field (name "PACKAGE / CASE") "0805")
        (field (name "MANUFACTURER") "Yageo")
      )
      (libsource (lib "ComponentDatabase") (part "RES"))
    )
    (comp (ref "SW1")
      (value "SWITCH_TACTILE_2PIN")
      (footprint "C&K_RS-282G05A3-SM_RT")
      (description "SWITCH TACTILE SPST-NO 0.05A 12V")
      (fields (field (name "PART NUMBER") "SSWI00022") (field (name "VOLTAGE") "12VDC"))
      (libsource (lib "ComponentDatabase") (part "SWITCH_TACTILE_2PIN"))
    )
    (comp (ref "SW2")
      (value "SWITCH_TACTILE_2PIN")
      (footprint "C&K_RS-282G05A3-SM_RT")
      (description "SWITCH TACTILE SPST-NO 0.05A 12V")
      (fields (field (name "PART NUMBER") "SSWI00022") (field (name "VOLTAGE") "12VDC"))
      (libsource (lib "ComponentDatabase") (part "SWITCH_TACTILE_2PIN"))
    )
    (comp (ref "X1")
      (value "25MHz")
      (footprint "HC-49/US")
      (description "CRYSTAL 25.0000MHZ 18PF T/H")
      (fields (field (name "PART NUMBER") "SCRY00016") (field (name "MANUFACTURER") "CTS-Frequency Controls"))
      (libsource (lib "ComponentDatabase") (part "CRYSTAL"))
    )
    (comp (ref "X2")
      (value "32.768kHz")
      (footprint "32.768_DIP")
      (description "CRYSTAL 32.768KHZ 6PF THRU")
      (fields (field (name "PART NUMBER") "SCRY00009") (field (name "MANUFACTURER") "Seiko Instruments"))
      (libsource (lib "ComponentDatabase") (part "CRYSTAL_32K"))
    )
  )
  (nets
    (net (code "1") (name "/I2C_SCL") (class "Default")
      (node (ref "CN4") (pin "10") (pinfunction "10_10") (pintype "passive"))
      (node (ref "IC2") (pin "6") (pinfunction "SCL_6") (pintype "input"))
      (node (ref "IC3") (pin "6") (pinfunction "SCL_6") (pintype "input"))
      (node (ref "IC4") (pin "6") (pinfunction "SCL_6") (pintype "input"))
      (node (ref "IC5") (pin "4") (pinfunction "SCL_4") (pintype "bidirectional"))
      (node (ref "R32") (pin "2") (pinfunction "2_2") (pintype "passive"))
    )
    (net (code "2") (name "/I2C_SDA") (class "Default")
      (node (ref "CN4") (pin "9") (pinfunction "9_9") (pintype "passive"))
      (node (ref "IC2") (pin "1") (pinfunction "SDA_1") (pintype "bidirectional"))
      (node (ref "IC3") (pin "5") (pinfunction "SDA_5") (pintype "bidirectional"))
      (node (ref "IC4") (pin "5") (pinfunction "SDA_5") (pintype "bidirectional"))
      (node (ref "IC5") (pin "6") (pinfunction "SDA_6") (pintype "bidirectional"))
      (node (ref "R33") (pin "2") (pinfunction "2_2") (pintype "passive"))
    )
    (net (code "3") (name "/LED1") (class "Default")
      (node (ref "CN2") (pin "1") (pinfunction "1_1") (pintype "passive"))
      (node (ref "LED1") (pin "2") (pinfunction "2_2") (pintype "passive"))
    )
    (net (code "4") (name "/LED2") (class "Default")
      (node (ref "CN2") (pin "2") (pinfunction "2_2") (pintype "passive"))
      (node (ref "LED2") (pin "2") (pinfunction "2_2") (pintype "passive"))
    )
    (net (code "5") (name "/LED3") (class "Default")
      (node (ref "CN2") (pin "3") (pinfunction "3_3") (pintype "passive"))
      (node (ref "LED3") (pin "2") (pinfunction "2_2") (pintype "passive"))
    )
    (net (code "6") (name "/LED4") (class "Default")
      (node (ref "CN2") (pin "4") (pinfunction "4_4") (pintype "passive"))
      (node (ref "LED4") (pin "2") (pinfunction "2_2") (pintype "passive"))
    )
    (net (code "7") (name "/LIGHT_INT") (class "Default")
      (node (ref "CN3") (pin "8") (pinfunction "8_8") (pintype "passive"))
      (node (ref "IC5") (pin "5") (pinfunction "INT_5") (pintype "output"))
    )
    (net (code "8") (name "/MICROSD_CS") (class "Default")
      (node (ref "CN3") (pin "5") (pinfunction "5_5") (pintype "passive"))
      (node (ref "CN6") (pin "2") (pinfunction "DAT3/~{CS}_2") (pintype "passive"))
      (node (ref "R34") (pin "2") (pinfunction "2_2") (pintype "passive"))
    )
    (net (code "9") (name "/RTC_INT") (class "Default")
      (node (ref "CN3") (pin "7") (pinfunction "7_7") (pintype "passive"))
      (node (ref "IC4") (pin "7") (pinfunction "~{INT}/CLKOUT_7") (pintype "output"))
    )
    (net (code "10") (name "/RXN") (class "Default")
      (node (ref "C12") (pin "2") (pinfunction "2_2") (pintype "passive"))
      (node (ref "R17") (pin "2") (pinfunction "2_2") (pintype "passive"))
      (node (ref "R26") (pin "1") (pinfunction "1_1") (pintype "passive"))
    )
    (net (code "11") (name "/RXP") (class "Default")
      (node (ref "C10") (pin "2") (pinfunction "2_2") (pintype "passive"))
      (node (ref "R18") (pin "2") (pinfunction "2_2") (pintype "passive"))
      (node (ref "R25") (pin "1") (pinfunction "1_1") (pintype "passive"))
    )
    (net (code "12") (name "/SPI_MISO") (class "Default")
      (node (ref "CN4") (pin "5") (pinfunction "5_5") (pintype "passive"))
      (node (ref "CN6") (pin "7") (pinfunction "DAT0/DO_7") (pintype "passive"))
      (node (ref "IC1") (pin "34") (pinfunction "MISO_34") (pintype "output"))
      (node (ref "R35") (pin "2") (pinfunction "2_2") (pintype "passive"))
    )
    (net (code "13") (name "/SPI_MOSI") (class "Default")
      (node (ref "CN4") (pin "4") (pinfunction "4_4") (pintype "passive"))
      (node (ref "CN6") (pin "3") (pinfunction "CMD/DI_3") (pintype "passive"))
      (node (ref "IC1") (pin "35") (pinfunction "MOSI_35") (pintype "input"))
      (node (ref "R36") (pin "2") (pinfunction "2_2") (pintype "passive"))
    )
    (net (code "14") (name "/SPI_SCK") (class "Default")
      (node (ref "CN4") (pin "6") (pinfunction "6_6") (pintype "passive"))
      (node (ref "CN6") (pin "5") (pinfunction "CLK/SCLK_5") (pintype "passive"))
      (node (ref "IC1") (pin "33") (pinfunction "SCLK_33") (pintype "input"))
      (node (ref "R37") (pin "2") (pinfunction "2_2") (pintype "passive"))
    )
    (net (code "15") (name "/TXN") (class "Default")
      (node (ref "CN5") (pin "2") (pinfunction "TD-_2") (pintype "passive"))
      (node (ref "R10") (pin "2") (pinfunction "2_2") (pintype "passive"))
      (node (ref "R15") (pin "2") (pinfunction "2_2") (pintype "passive"))
    )
    (net (code "16") (name "/TXP") (class "Default")
      (node (ref "CN5") (pin "1") (pinfunction "TD+_1") (pintype "passive"))
      (node (ref "R11") (pin "2") (pinfunction "2_2") (pintype "passive"))
      (node (ref "R16") (pin "2") (pinfunction "2_2") (pintype "passive"))
    )
    (net (code "17") (name "/USER_BUTTON") (class "Default")
      (node (ref "C17") (pin "2") (pinfunction "2_2") (pintype "passive"))
      (node (ref "CN3") (pin "3") (pinfunction "3_3") (pintype "passive"))
      (node (ref "R21") (pin "2") (pinfunction "2_2") (pintype "passive"))
      (node (ref "SW2") (pin "2") (pinfunction "2_2") (pintype "passive"))
    )
    (net (code "18") (name "/VIN") (class "Default")
      (node (ref "CN1") (pin "6") (pinfunction "6_6") (pintype "passive"))
    )
    (net (code "19") (name "/W5500_ACTLED") (class "Default")
      (node (ref "IC1") (pin "27") (pinfunction "ACTLED_27") (pintype "output"))
      (node (ref "R19") (pin "1") (pinfunction "1_1") (pintype "passive"))
    )
    (net (code "20") (name "/W5500_CS") (class "Default")
      (node (ref "CN4") (pin "3") (pinfunction "3_3") (pintype "passive"))
      (node (ref "IC1") (pin "32") (pinfunction "~{SCSn}_32") (pintype "input"))
      (node (ref "R14") (pin "2") (pinfunction "2_2") (pintype "passive"))
    )
    (net (code "21") (name "/W5500_INTn") (class "Default")
      (node (ref "CN4") (pin "2") (pinfunction "2_2") (pintype "passive"))
      (node (ref "IC1") (pin "36") (pinfunction "~{INT}n_36") (pintype "input"))
      (node (ref "R13") (pin "2") (pinfunction "2_2") (pintype "passive"))
    )
    (net (code "22") (name "/W5500_LINKLED") (class "Default")
      (node (ref "IC1") (pin "25") (pinfunction "LINKLED_25") (pintype "output"))
      (node (ref "R23") (pin "1") (pinfunction "1_1") (pintype "passive"))
    )
    (net (code "23") (name "/W5500_RST") (class "Default")
      (node (ref "CN4") (pin "1") (pinfunction "1_1") (pintype "passive"))
      (node (ref "IC1") (pin "37") (pinfunction "~{RSTn}_37") (pintype "input"))
      (node (ref "R9") (pin "1") (pinfunction "1_1") (pintype "passive"))
    )
    (net (code "24") (name "/~{RESET}") (class "Default")
      (node (ref "C16") (pin "2") (pinfunction "2_2") (pintype "passive"))
      (node (ref "CN1") (pin "1") (pinfunction "1_1") (pintype "passive"))
      (node (ref "R20") (pin "2") (pinfunction "2_2") (pintype "passive"))
      (node (ref "SW1") (pin "2") (pinfunction "2_2") (pintype "passive"))
    )
    (net (code "25") (name "3V3") (class "Default")
      (node (ref "C18") (pin "1") (pinfunction "1_1") (pintype "passive"))
      (node (ref "C22") (pin "2") (pinfunction "2_2") (pintype "passive"))
      (node (ref "C23") (pin "2") (pinfunction "2_2") (pintype "passive"))
      (node (ref "C25") (pin "2") (pinfunction "2_2") (pintype "passive"))
      (node (ref "C26") (pin "2") (pinfunction "2_2") (pintype "passive"))
      (node (ref "CN1") (pin "2") (pinfunction "2_2") (pintype "passive"))
      (node (ref "CN4") (pin "8") (pinfunction "8_8") (pintype "passive"))
      (node (ref "CN6") (pin "4") (pinfunction "VDD_4") (pintype "passive"))
      (node (ref "FB1") (pin "2") (pinfunction "2_2") (pintype "passive"))
      (node (ref "IC2") (pin "5") (pinfunction "VDD_5") (pintype "power_in"))
      (node (ref "IC3") (pin "8") (pinfunction "VCC_8") (pintype "power_in"))
      (node (ref "IC4") (pin "8") (pinfunction "VDD_8") (pintype "power_in"))
      (node (ref "IC5") (pin "1") (pinfunction "VDD_1") (pintype "power_in"))
      (node (ref "R20") (pin "1") (pinfunction "1_1") (pintype "passive"))
      (node (ref "R21") (pin "1") (pinfunction "1_1") (pintype "passive"))
      (node (ref "R32") (pin "1") (pinfunction "1_1") (pintype "passive"))
      (node (ref "R33") (pin "1") (pinfunction "1_1") (pintype "passive"))
      (node (ref "R34") (pin "1") (pinfunction "1_1") (pintype "passive"))
      (node (ref "R35") (pin "1") (pinfunction "1_1") (pintype "passive"))
      (node (ref "R36") (pin "1") (pinfunction "1_1") (pintype "passive"))
      (node (ref "R37") (pin "1") (pinfunction "1_1") (pintype "passive"))
    )
    (net (code "26") (name "3V3_W5500") (class "Default")
      (node (ref "C1") (pin "1") (pinfunction "1_1") (pintype "passive"))
      (node (ref "C13") (pin "1") (pinfunction "1_1") (pintype "passive"))
      (node (ref "C14") (pin "2") (pinfunction "2_2") (pintype "passive"))
      (node (ref "C2") (pin "2") (pinfunction "2_2") (pintype "passive"))
      (node (ref "C3") (pin "2") (pinfunction "2_2") (pintype "passive"))
      (node (ref "C4") (pin "2") (pinfunction "2_2") (pintype "passive"))
      (node (ref "C5") (pin "2") (pinfunction "2_2") (pintype "passive"))
      (node (ref "C6") (pin "2") (pinfunction "2_2") (pintype "passive"))
      (node (ref "C7") (pin "2") (pinfunction "2_2") (pintype "passive"))
      (node (ref "CN5") (pin "12") (pinfunction "Y+_12") (pintype "passive"))
      (node (ref "CN5") (pin "9") (pinfunction "G+_9") (pintype "passive"))
      (node (ref "FB1") (pin "1") (pinfunction "1_1") (pintype "passive"))
      (node (ref "IC1") (pin "11") (pinfunction "AVDD_11") (pintype "power_in"))
      (node (ref "IC1") (pin "15") (pinfunction "AVDD_15") (pintype "power_in"))
      (node (ref "IC1") (pin "17") (pinfunction "AVDD_17") (pintype "power_in"))
      (node (ref "IC1") (pin "21") (pinfunction "AVDD_21") (pintype "power_in"))
      (node (ref "IC1") (pin "28") (pinfunction "VDD_28") (pintype "power_in"))
      (node (ref "IC1") (pin "4") (pinfunction "AVDD_4") (pintype "power_in"))
      (node (ref "IC1") (pin "8") (pinfunction "AVDD_8") (pintype "power_in"))
      (node (ref "R10") (pin "1") (pinfunction "1_1") (pintype "passive"))
      (node (ref "R11") (pin "1") (pinfunction "1_1") (pintype "passive"))
      (node (ref "R12") (pin "1") (pinfunction "1_1") (pintype "passive"))
      (node (ref "R13") (pin "1") (pinfunction "1_1") (pintype "passive"))
      (node (ref "R14") (pin "1") (pinfunction "1_1") (pintype "passive"))
      (node (ref "R3") (pin "2") (pinfunction "2_2") (pintype "passive"))
      (node (ref "R5") (pin "2") (pinfunction "2_2") (pintype "passive"))
      (node (ref "R7") (pin "2") (pinfunction "2_2") (pintype "passive"))
      (node (ref "R9") (pin "2") (pinfunction "2_2") (pintype "passive"))
    )
    (net (code "27") (name "5V") (class "Default")
      (node (ref "CN1") (pin "3") (pinfunction "3_3") (pintype "passive"))
    )
    (net (code "28") (name "GND") (class "Default")
      (node (ref "BT1") (pin "2") (pinfunction "-_2") (pintype "passive"))
      (node (ref "C1") (pin "2") (pinfunction "2_2") (pintype "passive"))
      (node (ref "C11") (pin "2") (pinfunction "2_2") (pintype "passive"))
      (node (ref "C13") (pin "2") (pinfunction "2_2") (pintype "passive"))
      (node (ref "C14") (pin "1") (pinfunction "1_1") (pintype "passive"))
      (node (ref "C15") (pin "2") (pinfunction "2_2") (pintype "passive"))
      (node (ref "C16") (pin "1") (pinfunction "1_1") (pintype "passive"))
      (node (ref "C17") (pin "1") (pinfunction "1_1") (pintype "passive"))
      (node (ref "C18") (pin "2") (pinfunction "2_2") (pintype "passive"))
      (node (ref "C19") (pin "1") (pinfunction "1_1") (pintype "passive"))
      (node (ref "C2") (pin "1") (pinfunction "1_1") (pintype "passive"))
      (node (ref "C20") (pin "2") (pinfunction "2_2") (pintype "passive"))
      (node (ref "C21") (pin "1") (pinfunction "1_1") (pintype "passive"))
      (node (ref "C22") (pin "1") (pinfunction "1_1") (pintype "passive"))
      (node (ref "C23") (pin "1") (pinfunction "1_1") (pintype "passive"))
      (node (ref "C24") (pin "1") (pinfunction "1_1") (pintype "passive"))
      (node (ref "C25") (pin "1") (pinfunction "1_1") (pintype "passive"))
      (node (ref "C26") (pin "1") (pinfunction "1_1") (pintype "passive"))
      (node (ref "C27") (pin "1") (pinfunction "1_1") (pintype "passive"))
      (node (ref "C3") (pin "1") (pinfunction "1_1") (pintype "passive"))
      (node (ref "C4") (pin "1") (pinfunction "1_1") (pintype "passive"))
      (node (ref "C5") (pin "1") (pinfunction "1_1") (pintype "passive"))
      (node (ref "C6") (pin "1") (pinfunction "1_1") (pintype "passive"))
      (node (ref "C7") (pin "1") (pinfunction "1_1") (pintype "passive"))
      (node (ref "C8") (pin "2") (pinfunction "2_2") (pintype "passive"))
      (node (ref "C9") (pin "2") (pinfunction "2_2") (pintype "passive"))
      (node (ref "CN1") (pin "4") (pinfunction "4_4") (pintype "passive"))
      (node (ref "CN1") (pin "5") (pinfunction "5_5") (pintype "passive"))
      (node (ref "CN4") (pin "7") (pinfunction "7_7") (pintype "passive"))
      (node (ref "CN6") (pin "10") (pinfunction "GND_10") (pintype "passive"))
      (node (ref "CN6") (pin "6") (pinfunction "VSS_6") (pintype "passive"))
      (node (ref "CN6") (pin "9") (pinfunction "CD_9") (pintype "passive"))
      (node (ref "IC1") (pin "14") (pinfunction "AGND_14") (pintype "power_in"))
      (node (ref "IC1") (pin "16") (pinfunction "AGND_16") (pintype "power_in"))
      (node (ref "IC1") (pin "19") (pinfunction "AGND_19") (pintype "power_in"))
      (node (ref "IC1") (pin "29") (pinfunction "GND_29") (pintype "power_in"))
      (node (ref "IC1") (pin "3") (pinfunction "AGND_3") (pintype "power_in"))
      (node (ref "IC1") (pin "48") (pinfunction "AGND_48") (pintype "power_in"))
      (node (ref "IC1") (pin "9") (pinfunction "AGND_9") (pintype "power_in"))
      (node (ref "IC2") (pin "2") (pinfunction "VSS_2") (pintype "power_in"))
      (node (ref "IC2") (pin "7") (pinfunction "EP_7") (pintype "passive"))
      (node (ref "IC3") (pin "1") (pinfunction "A0_1") (pintype "input"))
      (node (ref "IC3") (pin "2") (pinfunction "A1_2") (pintype "input"))
      (node (ref "IC3") (pin "3") (pinfunction "NC_3") (pintype "passive"))
      (node (ref "IC3") (pin "4") (pinfunction "GND_4") (pintype "power_in"))
      (node (ref "IC3") (pin "7") (pinfunction "WP_7") (pintype "input"))
      (node (ref "IC4") (pin "4") (pinfunction "VSS_4") (pintype "power_in"))
      (node (ref "IC4") (pin "9") (pinfunction "EP_9") (pintype "passive"))
      (node (ref "IC5") (pin "2") (pinfunction "ADDR_2") (pintype "input"))
      (node (ref "IC5") (pin "3") (pinfunction "GND_3") (pintype "power_in"))
      (node (ref "R1") (pin "2") (pinfunction "2_2") (pintype "passive"))
      (node (ref "R2") (pin "2") (pinfunction "2_2") (pintype "passive"))
      (node (ref "R24") (pin "2") (pinfunction "2_2") (pintype "passive"))
      (node (ref "R27") (pin "2") (pinfunction "2_2") (pintype "passive"))
      (node (ref "R28") (pin "2") (pinfunction "2_2") (pintype "passive"))
      (node (ref "R29") (pin "1") (pinfunction "1_1") (pintype "passive"))
      (node (ref "R30") (pin "1") (pinfunction "1_1") (pintype "passive"))
      (node (ref "R31") (pin "1") (pinfunction "1_1") (pintype "passive"))
      (node (ref "R4") (pin "2") (pinfunction "2_2") (pintype "passive"))
      (node (ref "R6") (pin "2") (pinfunction "2_2") (pintype "passive"))
      (node (ref "R8") (pin "2") (pinfunction "2_2") (pintype "passive"))
      (node (ref "SW1") (pin "1") (pinfunction "1_1") (pintype "passive"))
      (node (ref "SW2") (pin "1") (pinfunction "1_1") (pintype "passive"))
      (node (ref "X2") (pin "3") (pinfunction "3_3") (pintype "power_in"))
    )
    (net (code "29") (name "Net-(BT1-+)") (class "Default")
      (node (ref "BT1") (pin "1") (pinfunction "+_1") (pintype "passive"))
      (node (ref "IC4") (pin "3") (pinfunction "VBAT_3") (pintype "power_in"))
    )
    (net (code "30") (name "Net-(C15-Pad1)") (class "Default")
      (node (ref "C15") (pin "1") (pinfunction "1_1") (pintype "passive"))
      (node (ref "CN5") (pin "13") (pinfunction "GND_13") (pintype "power_in"))
      (node (ref "CN5") (pin "14") (pinfunction "GND_14") (pintype "power_in"))
      (node (ref "CN5") (pin "7") (pinfunction "GND_7") (pintype "power_in"))
      (node (ref "CN5") (pin "8") (pinfunction "GND_8") (pintype "power_in"))
    )
    (net (code "31") (name "Net-(CN5-CTRD)") (class "Default")
      (node (ref "C19") (pin "2") (pinfunction "2_2") (pintype "passive"))
      (node (ref "CN5") (pin "5") (pinfunction "CTRD_5") (pintype "passive"))
      (node (ref "R25") (pin "2") (pinfunction "2_2") (pintype "passive"))
      (node (ref "R26") (pin "2") (pinfunction "2_2") (pintype "passive"))
    )
    (net (code "32") (name "Net-(CN5-CTTD)") (class "Default")
      (node (ref "C8") (pin "1") (pinfunction "1_1") (pintype "passive"))
      (node (ref "CN5") (pin "4") (pinfunction "CTTD_4") (pintype "passive"))
      (node (ref "R12") (pin "2") (pinfunction "2_2") (pintype "passive"))
    )
    (net (code "33") (name "Net-(CN5-G-)") (class "Default")
      (node (ref "CN5") (pin "10") (pinfunction "G-_10") (pintype "passive"))
      (node (ref "R19") (pin "2") (pinfunction "2_2") (pintype "passive"))
    )
    (net (code "34") (name "Net-(CN5-RD+)") (class "Default")
      (node (ref "C10") (pin "1") (pinfunction "1_1") (pintype "passive"))
      (node (ref "CN5") (pin "3") (pinfunction "RD+_3") (pintype "passive"))
    )
    (net (code "35") (name "Net-(CN5-RD-)") (class "Default")
      (node (ref "C12") (pin "1") (pinfunction "1_1") (pintype "passive"))
      (node (ref "CN5") (pin "6") (pinfunction "RD-_6") (pintype "passive"))
    )
    (net (code "36") (name "Net-(CN5-Y-)") (class "Default")
      (node (ref "CN5") (pin "11") (pinfunction "Y-_11") (pintype "passive"))
      (node (ref "R23") (pin "2") (pinfunction "2_2") (pintype "passive"))
    )
    (net (code "37") (name "Net-(IC1-1V2O)") (class "Default")
      (node (ref "C21") (pin "2") (pinfunction "2_2") (pintype "passive"))
      (node (ref "IC1") (pin "22") (pinfunction "1V2O_22") (pintype "output"))
    )
    (net (code "38") (name "Net-(IC1-EXRES1)") (class "Default")
      (node (ref "IC1") (pin "10") (pinfunction "EXRES1_10") (pintype "bidirectional"))
      (node (ref "R24") (pin "1") (pinfunction "1_1") (pintype "passive"))
    )
    (net (code "39") (name "Net-(IC1-PMODE0)") (class "Default")
      (node (ref "IC1") (pin "45") (pinfunction "PMODE0_45") (pintype "input"))
      (node (ref "R7") (pin "1") (pinfunction "1_1") (pintype "passive"))
    )
    (net (code "40") (name "Net-(IC1-PMODE1)") (class "Default")
      (node (ref "IC1") (pin "44") (pinfunction "PMODE1_44") (pintype "input"))
      (node (ref "R5") (pin "1") (pinfunction "1_1") (pintype "passive"))
    )
    (net (code "41") (name "Net-(IC1-PMODE2)") (class "Default")
      (node (ref "IC1") (pin "43") (pinfunction "PMODE2_43") (pintype "input"))
      (node (ref "R3") (pin "1") (pinfunction "1_1") (pintype "passive"))
    )
    (net (code "42") (name "Net-(IC1-RSVD-Pad23)") (class "Default")
      (node (ref "IC1") (pin "23") (pinfunction "RSVD_23") (pintype "input"))
      (node (ref "R27") (pin "1") (pinfunction "1_1") (pintype "passive"))
    )
    (net (code "43") (name "Net-(IC1-RSVD-Pad38)") (class "Default")
      (node (ref "IC1") (pin "38") (pinfunction "RSVD_38") (pintype "input"))
      (node (ref "R8") (pin "1") (pinfunction "1_1") (pintype "passive"))
    )
    (net (code "44") (name "Net-(IC1-RSVD-Pad39)") (class "Default")
      (node (ref "IC1") (pin "39") (pinfunction "RSVD_39") (pintype "input"))
      (node (ref "R6") (pin "1") (pinfunction "1_1") (pintype "passive"))
    )
    (net (code "45") (name "Net-(IC1-RSVD-Pad40)") (class "Default")
      (node (ref "IC1") (pin "40") (pinfunction "RSVD_40") (pintype "input"))
      (node (ref "R4") (pin "1") (pinfunction "1_1") (pintype "passive"))
    )
    (net (code "46") (name "Net-(IC1-RSVD-Pad41)") (class "Default")
      (node (ref "IC1") (pin "41") (pinfunction "RSVD_41") (pintype "input"))
      (node (ref "R2") (pin "1") (pinfunction "1_1") (pintype "passive"))
    )
    (net (code "47") (name "Net-(IC1-RSVD-Pad42)") (class "Default")
      (node (ref "IC1") (pin "42") (pinfunction "RSVD_42") (pintype "input"))
      (node (ref "R1") (pin "1") (pinfunction "1_1") (pintype "passive"))
    )
    (net (code "48") (name "Net-(IC1-RXN)") (class "Default")
      (node (ref "IC1") (pin "5") (pinfunction "RXN_5") (pintype "output"))
      (node (ref "R17") (pin "1") (pinfunction "1_1") (pintype "passive"))
    )
    (net (code "49") (name "Net-(IC1-RXP)") (class "Default")
      (node (ref "IC1") (pin "6") (pinfunction "RXP_6") (pintype "output"))
      (node (ref "R18") (pin "1") (pinfunction "1_1") (pintype "passive"))
    )
    (net (code "50") (name "Net-(IC1-TOCAP)") (class "Default")
      (node (ref "C20") (pin "1") (pinfunction "1_1") (pintype "passive"))
      (node (ref "IC1") (pin "20") (pinfunction "TOCAP_20") (pintype "output"))
    )
    (net (code "51") (name "Net-(IC1-TXN)") (class "Default")
      (node (ref "IC1") (pin "1") (pinfunction "TXN_1") (pintype "output"))
      (node (ref "R15") (pin "1") (pinfunction "1_1") (pintype "passive"))
    )
    (net (code "52") (name "Net-(IC1-TXP)") (class "Default")
      (node (ref "IC1") (pin "2") (pinfunction "TXP_2") (pintype "output"))
      (node (ref "R16") (pin "1") (pinfunction "1_1") (pintype "passive"))
    )
    (net (code "53") (name "Net-(IC1-XI{slash}CLKIN)") (class "Default")
      (node (ref "C11") (pin "1") (pinfunction "1_1") (pintype "passive"))
      (node (ref "IC1") (pin "30") (pinfunction "XI/CLKIN_30") (pintype "input"))
      (node (ref "X1") (pin "2") (pinfunction "2_2") (pintype "passive"))
    )
    (net (code "54") (name "Net-(IC1-XO)") (class "Default")
      (node (ref "C9") (pin "1") (pinfunction "1_1") (pintype "passive"))
      (node (ref "IC1") (pin "31") (pinfunction "XO_31") (pintype "output"))
      (node (ref "X1") (pin "1") (pinfunction "1_1") (pintype "passive"))
    )
    (net (code "55") (name "Net-(IC4-OSCI)") (class "Default")
      (node (ref "C24") (pin "2") (pinfunction "2_2") (pintype "passive"))
      (node (ref "IC4") (pin "1") (pinfunction "OSCI_1") (pintype "input"))
      (node (ref "X2") (pin "2") (pinfunction "2_2") (pintype "passive"))
    )
    (net (code "56") (name "Net-(IC4-OSCO)") (class "Default")
      (node (ref "C27") (pin "2") (pinfunction "2_2") (pintype "passive"))
      (node (ref "IC4") (pin "2") (pinfunction "OSCO_2") (pintype "output"))
      (node (ref "X2") (pin "1") (pinfunction "1_1") (pintype "passive"))
    )
    (net (code "57") (name "Net-(LED1-Pad1)") (class "Default")
      (node (ref "LED1") (pin "1") (pinfunction "1_1") (pintype "passive"))
      (node (ref "R28") (pin "1") (pinfunction "1_1") (pintype "passive"))
    )
    (net (code "58") (name "Net-(LED2-Pad1)") (class "Default")
      (node (ref "LED2") (pin "1") (pinfunction "1_1") (pintype "passive"))
      (node (ref "R29") (pin "2") (pinfunction "2_2") (pintype "passive"))
    )
    (net (code "59") (name "Net-(LED3-Pad1)") (class "Default")
      (node (ref "LED3") (pin "1") (pinfunction "1_1") (pintype "passive"))
      (node (ref "R30") (pin "2") (pinfunction "2_2") (pintype "passive"))
    )
    (net (code "60") (name "Net-(LED4-Pad1)") (class "Default")
      (node (ref "LED4") (pin "1") (pinfunction "1_1") (pintype "passive"))
      (node (ref "R31") (pin "2") (pinfunction "2_2") (pintype "passive"))
    )
    (net (code "61") (name "unconnected-(CN2-Pad5)") (class "Default")
      (node (ref "CN2") (pin "5") (pinfunction "5_5") (pintype "passive"))
    )
    (net (code "62") (name "unconnected-(CN2-Pad6)") (class "Default")
      (node (ref "CN2") (pin "6") (pinfunction "6_6") (pintype "passive"))
    )
    (net (code "63") (name "unconnected-(CN3-Pad1)") (class "Default")
      (node (ref "CN3") (pin "1") (pinfunction "1_1") (pintype "passive"))
    )
    (net (code "64") (name "unconnected-(CN3-Pad2)") (class "Default")
      (node (ref "CN3") (pin "2") (pinfunction "2_2") (pintype "passive"))
    )
    (net (code "65") (name "unconnected-(CN3-Pad4)") (class "Default")
      (node (ref "CN3") (pin "4") (pinfunction "4_4") (pintype "passive"))
    )
    (net (code "66") (name "unconnected-(CN3-Pad6)") (class "Default")
      (node (ref "CN3") (pin "6") (pinfunction "6_6") (pintype "passive"))
    )
    (net (code "67") (name "unconnected-(CN6-DAT1{slash}NC-Pad8)") (class "Default")
      (node (ref "CN6") (pin "8") (pinfunction "DAT1/NC_8") (pintype "passive"))
    )
    (net (code "68") (name "unconnected-(CN6-DAT2{slash}NC-Pad1)") (class "Default")
      (node (ref "CN6") (pin "1") (pinfunction "DAT2/NC_1") (pintype "passive"))
    )
    (net (code "69") (name "unconnected-(IC1-DUPLED-Pad26)") (class "Default")
      (node (ref "IC1") (pin "26") (pinfunction "DUPLED_26") (pintype "output+no_connect"))
    )
    (net (code "70") (name "unconnected-(IC1-NC-Pad7)") (class "Default")
      (node (ref "IC1") (pin "7") (pinfunction "NC_7") (pintype "passive+no_connect"))
    )
    (net (code "71") (name "unconnected-(IC1-NC-Pad12)") (class "Default")
      (node (ref "IC1") (pin "12") (pinfunction "NC_12") (pintype "passive+no_connect"))
    )
    (net (code "72") (name "unconnected-(IC1-NC-Pad13)") (class "Default")
      (node (ref "IC1") (pin "13") (pinfunction "NC_13") (pintype "passive+no_connect"))
    )
    (net (code "73") (name "unconnected-(IC1-NC-Pad46)") (class "Default")
      (node (ref "IC1") (pin "46") (pinfunction "NC_46") (pintype "input+no_connect"))
    )
    (net (code "74") (name "unconnected-(IC1-NC-Pad47)") (class "Default")
      (node (ref "IC1") (pin "47") (pinfunction "NC_47") (pintype "input+no_connect"))
    )
    (net (code "75") (name "unconnected-(IC1-SPDLED-Pad24)") (class "Default")
      (node (ref "IC1") (pin "24") (pinfunction "SPDLED_24") (pintype "output+no_connect"))
    )
    (net (code "76") (name "unconnected-(IC1-VBG-Pad18)") (class "Default")
      (node (ref "IC1") (pin "18") (pinfunction "VBG_18") (pintype "output+no_connect"))
    )
    (net (code "77") (name "unconnected-(IC2-NC-Pad3)") (class "Default")
      (node (ref "IC2") (pin "3") (pinfunction "NC_3") (pintype "passive"))
    )
    (net (code "78") (name "unconnected-(IC2-NC-Pad4)") (class "Default")
      (node (ref "IC2") (pin "4") (pinfunction "NC_4") (pintype "passive"))
    )
  )
)
